# 07-_--.net
KiCad netlist of a schematic drawn in Altium Designer
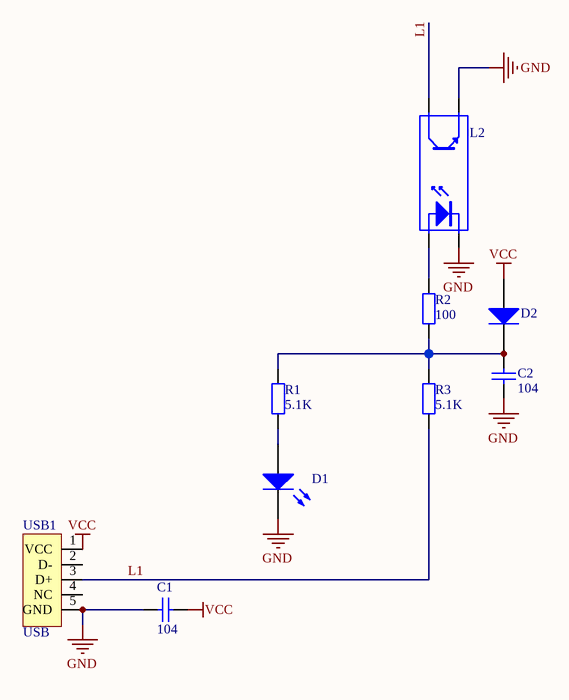
[diagram p0: 07-寻迹传感器模块--原理图.SchDoc]

(export (version "E")
  (design (tool "Eeschema 10.0.6"))
  (components
    (comp (ref "C1")
      (value "104")
      (footprint "0805")
      (description "Capacitor")
      (fields (field (name "Comment") "Cap") (field (name "PUBLISHER") "Altium Limited"))
      (libsource (lib "Miscellaneous Devices") (part "Cap"))
    )
    (comp (ref "C2")
      (value "104")
      (footprint "0805")
      (description "Capacitor")
      (fields (field (name "Comment") "Cap") (field (name "PUBLISHER") "Altium Limited"))
      (libsource (lib "Miscellaneous Devices") (part "Cap"))
    )
    (comp (ref "D1")
      (value "LED0")
      (footprint "0805")
      (description "Typical INFRARED GaAs LED")
      (fields (field (name "PUBLISHER") "Altium Limited"))
      (libsource (lib "Miscellaneous Devices") (part "LED0"))
    )
    (comp (ref "D2")
      (value "Diode")
      (footprint "0805")
      (description "Default Diode")
      (fields (field (name "PUBLISHER") "Altium Limited"))
      (libsource (lib "Miscellaneous Devices") (part "Diode"))
    )
    (comp (ref "L2")
      (value "Optoisolator1")
      (footprint "Red")
      (description "4-Pin Phototransistor Optocoupler")
      (fields (field (name "PUBLISHER") "Altium Limited"))
      (libsource (lib "Miscellaneous Devices") (part "Optoisolator1"))
    )
    (comp (ref "R1")
      (value "5.1K")
      (footprint "0805")
      (description "Resistor")
      (fields (field (name "Comment") "res2") (field (name "PUBLISHER") "Altium Limited"))
      (libsource (lib "Miscellaneous Devices") (part "Res2"))
    )
    (comp (ref "R2")
      (value "100")
      (footprint "0805")
      (description "Resistor")
      (fields (field (name "Comment") "res2") (field (name "PUBLISHER") "Altium Limited"))
      (libsource (lib "Miscellaneous Devices") (part "Res2"))
    )
    (comp (ref "R3")
      (value "5.1K")
      (footprint "0805")
      (description "Resistor")
      (fields (field (name "Comment") "res2") (field (name "PUBLISHER") "Altium Limited"))
      (libsource (lib "Miscellaneous Devices") (part "Res2"))
    )
    (comp (ref "USB1") (value "USB") (footprint "USB/SM0.8-6H5") (libsource (lib "原理图库") (part "USB5")))
  )
  (nets
    (net (code "1") (name "/L1") (class "Default")
      (node (ref "L2") (pin "4") (pinfunction "C_4") (pintype "passive"))
      (node (ref "R3") (pin "2") (pinfunction "2_2") (pintype "passive"))
      (node (ref "USB1") (pin "3") (pinfunction "D+_3") (pintype "passive"))
    )
    (net (code "2") (name "GND") (class "Default")
      (node (ref "C1") (pin "2") (pinfunction "2_2") (pintype "passive"))
      (node (ref "C2") (pin "2") (pinfunction "2_2") (pintype "passive"))
      (node (ref "D1") (pin "2") (pinfunction "K_2") (pintype "passive"))
      (node (ref "L2") (pin "2") (pinfunction "K_2") (pintype "passive"))
      (node (ref "L2") (pin "3") (pinfunction "E_3") (pintype "passive"))
      (node (ref "USB1") (pin "5") (pinfunction "GND_5") (pintype "passive"))
    )
    (net (code "3") (name "Net-(D1-A)") (class "Default")
      (node (ref "D1") (pin "1") (pinfunction "A_1") (pintype "passive"))
      (node (ref "R1") (pin "2") (pinfunction "2_2") (pintype "passive"))
    )
    (net (code "4") (name "Net-(D2-K)") (class "Default")
      (node (ref "C2") (pin "1") (pinfunction "1_1") (pintype "passive"))
      (node (ref "D2") (pin "2") (pinfunction "K_2") (pintype "passive"))
      (node (ref "R1") (pin "1") (pinfunction "1_1") (pintype "passive"))
      (node (ref "R2") (pin "2") (pinfunction "2_2") (pintype "passive"))
      (node (ref "R3") (pin "1") (pinfunction "1_1") (pintype "passive"))
    )
    (net (code "5") (name "Net-(L2-A)") (class "Default")
      (node (ref "L2") (pin "1") (pinfunction "A_1") (pintype "passive"))
      (node (ref "R2") (pin "1") (pinfunction "1_1") (pintype "passive"))
    )
    (net (code "6") (name "VCC") (class "Default")
      (node (ref "C1") (pin "1") (pinfunction "1_1") (pintype "passive"))
      (node (ref "D2") (pin "1") (pinfunction "A_1") (pintype "passive"))
      (node (ref "USB1") (pin "1") (pinfunction "VCC_1") (pintype "passive"))
    )
    (net (code "7") (name "unconnected-(USB1-D--Pad2)") (class "Default")
      (node (ref "USB1") (pin "2") (pinfunction "D-_2") (pintype "passive"))
    )
    (net (code "8") (name "unconnected-(USB1-NC-Pad4)") (class "Default")
      (node (ref "USB1") (pin "4") (pinfunction "NC_4") (pintype "passive"))
    )
  )
)
